# MUS-1099.net
KiCad netlist of a schematic drawn in EAGLE
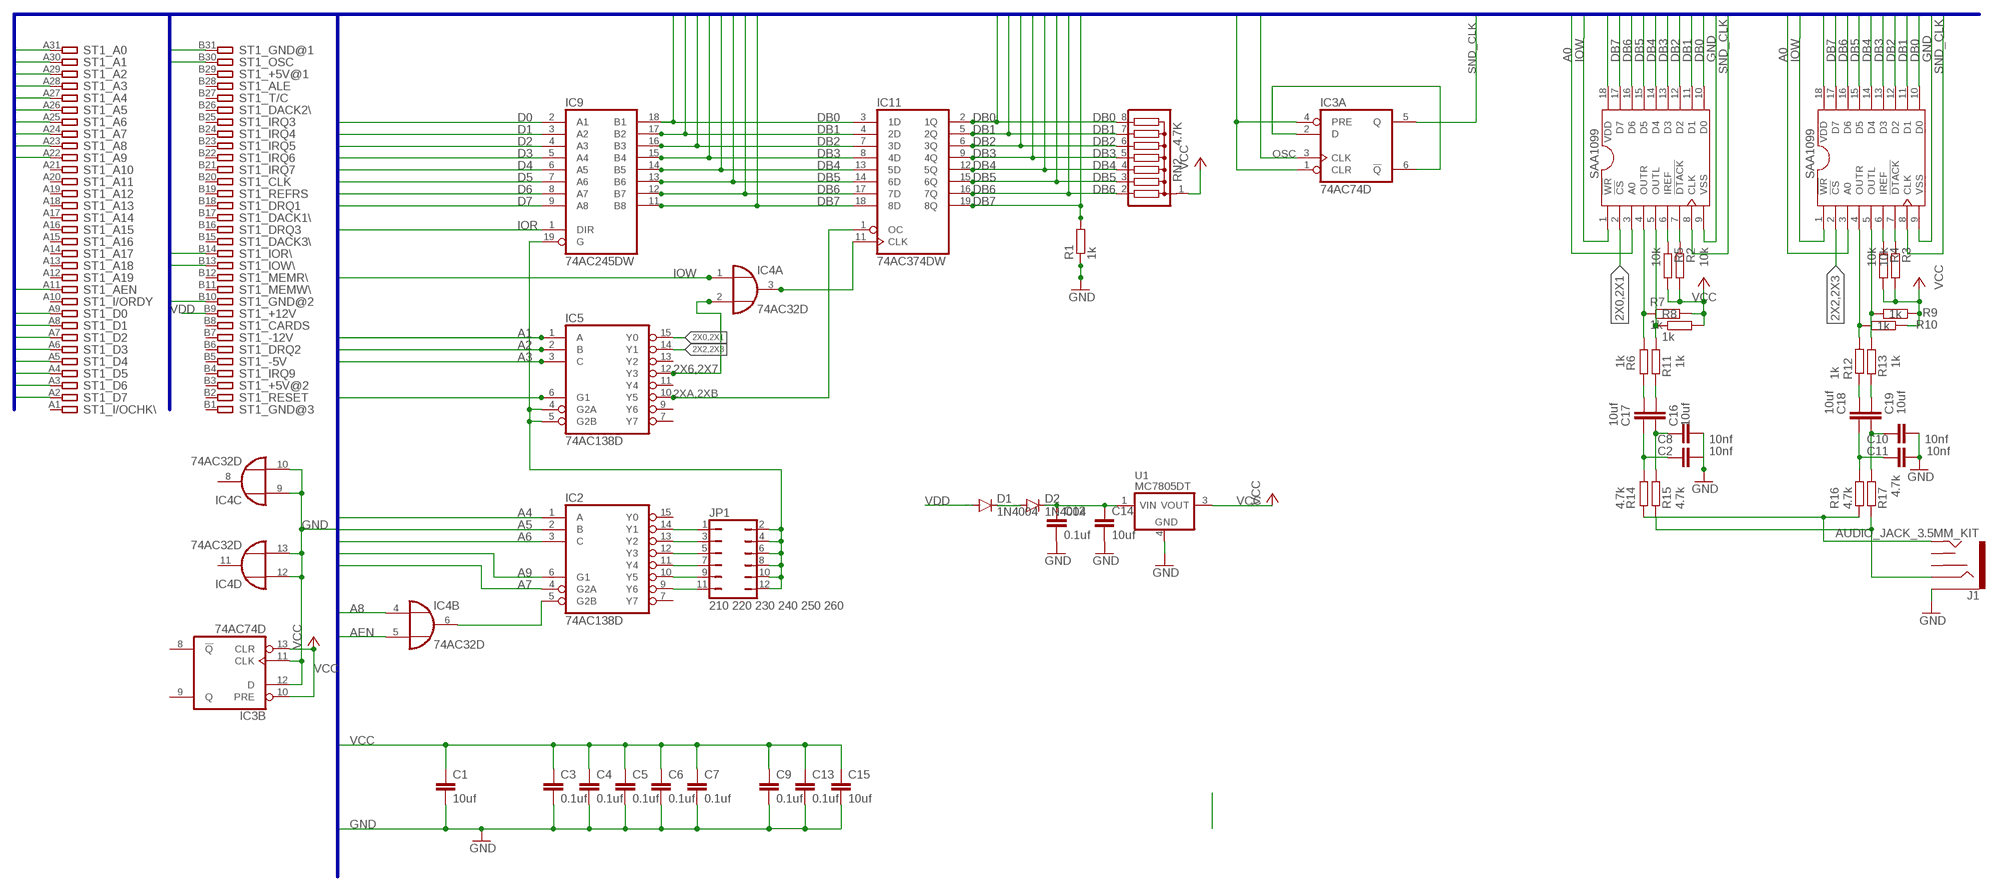
[diagram p0: schematic, sheet 1]

(export (version "E")
  (design (tool "Eeschema 10.0.6"))
  (components
    (comp (ref "C1")
      (value "10uf")
      (footprint "eagle-import:C0805")
      (libsource (lib "eagle-import") (part "C-EUC0805"))
    )
    (comp (ref "C2")
      (value "10nf")
      (footprint "eagle-import:C0805K")
      (libsource (lib "eagle-import") (part "C-EUC0805K"))
    )
    (comp (ref "C3")
      (value "0.1uf")
      (footprint "eagle-import:C0805")
      (libsource (lib "eagle-import") (part "C-EUC0805"))
    )
    (comp (ref "C4")
      (value "0.1uf")
      (footprint "eagle-import:C0805")
      (libsource (lib "eagle-import") (part "C-EUC0805"))
    )
    (comp (ref "C5")
      (value "0.1uf")
      (footprint "eagle-import:C0805")
      (libsource (lib "eagle-import") (part "C-EUC0805"))
    )
    (comp (ref "C6")
      (value "0.1uf")
      (footprint "eagle-import:C0805")
      (libsource (lib "eagle-import") (part "C-EUC0805"))
    )
    (comp (ref "C7")
      (value "0.1uf")
      (footprint "eagle-import:C0805")
      (libsource (lib "eagle-import") (part "C-EUC0805"))
    )
    (comp (ref "C8")
      (value "10nf")
      (footprint "eagle-import:C0805K")
      (libsource (lib "eagle-import") (part "C-EUC0805K"))
    )
    (comp (ref "C9")
      (value "0.1uf")
      (footprint "eagle-import:C0805")
      (libsource (lib "eagle-import") (part "C-EUC0805"))
    )
    (comp (ref "C10")
      (value "10nf")
      (footprint "eagle-import:C0805K")
      (libsource (lib "eagle-import") (part "C-EUC0805K"))
    )
    (comp (ref "C11")
      (value "10nf")
      (footprint "eagle-import:C0805K")
      (libsource (lib "eagle-import") (part "C-EUC0805K"))
    )
    (comp (ref "C12")
      (value "0.1uf")
      (footprint "eagle-import:C0805")
      (libsource (lib "eagle-import") (part "C-EUC0805"))
    )
    (comp (ref "C13")
      (value "0.1uf")
      (footprint "eagle-import:C0805")
      (libsource (lib "eagle-import") (part "C-EUC0805"))
    )
    (comp (ref "C14")
      (value "10uf")
      (footprint "eagle-import:C0805K")
      (libsource (lib "eagle-import") (part "C-EUC0805K"))
    )
    (comp (ref "C15")
      (value "10uf")
      (footprint "eagle-import:C0805K")
      (libsource (lib "eagle-import") (part "C-EUC0805K"))
    )
    (comp (ref "C16")
      (value "10uf")
      (footprint "eagle-import:C0805K")
      (libsource (lib "eagle-import") (part "C-EUC0805K"))
    )
    (comp (ref "C17")
      (value "10uf")
      (footprint "eagle-import:C0805K")
      (libsource (lib "eagle-import") (part "C-EUC0805K"))
    )
    (comp (ref "C18")
      (value "10uf")
      (footprint "eagle-import:C0805K")
      (libsource (lib "eagle-import") (part "C-EUC0805K"))
    )
    (comp (ref "C19")
      (value "10uf")
      (footprint "eagle-import:C0805K")
      (libsource (lib "eagle-import") (part "C-EUC0805K"))
    )
    (comp (ref "D1")
      (value "1N4004")
      (footprint "eagle-import:DO41-10")
      (libsource (lib "eagle-import") (part "1N4004"))
    )
    (comp (ref "D2")
      (value "1N4004")
      (footprint "eagle-import:DO41-10")
      (libsource (lib "eagle-import") (part "1N4004"))
    )
    (comp (ref "IC2")
      (value "74AC138D")
      (footprint "eagle-import:SO16")
      (libsource (lib "eagle-import") (part "74138DAC"))
    )
    (comp (ref "IC3")
      (value "74AC74D")
      (footprint "eagle-import:SO14")
      (libsource (lib "eagle-import") (part "7474DAC"))
    )
    (comp (ref "IC4")
      (value "74AC32D")
      (footprint "eagle-import:SO14")
      (libsource (lib "eagle-import") (part "7432DAC"))
    )
    (comp (ref "IC5")
      (value "74AC138D")
      (footprint "eagle-import:SO16")
      (libsource (lib "eagle-import") (part "74138DAC"))
    )
    (comp (ref "IC7")
      (value "SAA1099")
      (footprint "eagle-import:DIL18")
      (libsource (lib "eagle-import") (part "SAA1099"))
    )
    (comp (ref "IC8")
      (value "SAA1099")
      (footprint "eagle-import:DIL18")
      (libsource (lib "eagle-import") (part "SAA1099"))
    )
    (comp (ref "IC9")
      (value "74AC245DW")
      (footprint "eagle-import:SO20W")
      (libsource (lib "eagle-import") (part "74245DWAC"))
    )
    (comp (ref "IC11")
      (value "74AC374DW")
      (footprint "eagle-import:SO20W")
      (libsource (lib "eagle-import") (part "74374DWAC"))
    )
    (comp (ref "J1")
      (value "AUDIO_JACK_3.5MM_KIT")
      (footprint "eagle-import:AUDIO-JACK-KIT")
      (libsource (lib "eagle-import") (part "AUDIO_JACK_3.5MM_KIT"))
    )
    (comp (ref "JP1")
      (value "210 220 230 240 250 260")
      (footprint "eagle-import:JP6Q")
      (libsource (lib "eagle-import") (part "JP6Q"))
    )
    (comp (ref "R1")
      (value "1k")
      (footprint "eagle-import:R0805")
      (libsource (lib "eagle-import") (part "R-EU_R0805"))
    )
    (comp (ref "R2")
      (value "10k")
      (footprint "eagle-import:R0805")
      (libsource (lib "eagle-import") (part "R-EU_R0805"))
    )
    (comp (ref "R3")
      (value "10k")
      (footprint "eagle-import:R0805")
      (libsource (lib "eagle-import") (part "R-EU_R0805"))
    )
    (comp (ref "R4")
      (value "10k")
      (footprint "eagle-import:R0805")
      (libsource (lib "eagle-import") (part "R-EU_R0805"))
    )
    (comp (ref "R5")
      (value "10k")
      (footprint "eagle-import:R0805")
      (libsource (lib "eagle-import") (part "R-EU_R0805"))
    )
    (comp (ref "R6")
      (value "1k")
      (footprint "eagle-import:R0805")
      (libsource (lib "eagle-import") (part "R-EU_R0805"))
    )
    (comp (ref "R7")
      (value "1k")
      (footprint "eagle-import:R0805")
      (libsource (lib "eagle-import") (part "R-EU_R0805"))
    )
    (comp (ref "R8")
      (value "1k")
      (footprint "eagle-import:R0805")
      (libsource (lib "eagle-import") (part "R-EU_R0805"))
    )
    (comp (ref "R9")
      (value "1k")
      (footprint "eagle-import:R0805")
      (libsource (lib "eagle-import") (part "R-EU_R0805"))
    )
    (comp (ref "R10")
      (value "1k")
      (footprint "eagle-import:R0805")
      (libsource (lib "eagle-import") (part "R-EU_R0805"))
    )
    (comp (ref "R11")
      (value "1k")
      (footprint "eagle-import:R0805")
      (libsource (lib "eagle-import") (part "R-EU_R0805"))
    )
    (comp (ref "R12")
      (value "1k")
      (footprint "eagle-import:R0805")
      (libsource (lib "eagle-import") (part "R-EU_R0805"))
    )
    (comp (ref "R13")
      (value "1k")
      (footprint "eagle-import:R0805")
      (libsource (lib "eagle-import") (part "R-EU_R0805"))
    )
    (comp (ref "R14")
      (value "4.7k")
      (footprint "eagle-import:R0805")
      (libsource (lib "eagle-import") (part "R-EU_R0805"))
    )
    (comp (ref "R15")
      (value "4.7k")
      (footprint "eagle-import:R0805")
      (libsource (lib "eagle-import") (part "R-EU_R0805"))
    )
    (comp (ref "R16")
      (value "4.7k")
      (footprint "eagle-import:R0805")
      (libsource (lib "eagle-import") (part "R-EU_R0805"))
    )
    (comp (ref "R17")
      (value "4.7k")
      (footprint "eagle-import:R0805")
      (libsource (lib "eagle-import") (part "R-EU_R0805"))
    )
    (comp (ref "RN2")
      (value "4.7K")
      (footprint "eagle-import:SIL8")
      (libsource (lib "eagle-import") (part "G07R"))
    )
    (comp (ref "ST1")
      (value "8 bit ISA")
      (footprint "eagle-import:IBM8BIT")
      (libsource (lib "eagle-import") (part "IBM8BIT"))
    )
    (comp (ref "U1")
      (value "MC7805DT")
      (footprint "eagle-import:DPAK-3")
      (libsource (lib "eagle-import") (part "MC78DT05"))
    )
  )
  (nets
    (net (code "1") (name "/2X6,2X7") (class "Default")
      (node (ref "IC4") (pin "2") (pinfunction "I1_2") (pintype "input"))
      (node (ref "IC5") (pin "12") (pinfunction "Y3_12") (pintype "output"))
    )
    (net (code "2") (name "/2XA,2XB") (class "Default")
      (node (ref "IC11") (pin "1") (pinfunction "OC_1") (pintype "input"))
      (node (ref "IC5") (pin "10") (pinfunction "Y5_10") (pintype "output"))
    )
    (net (code "3") (name "/A0") (class "Default")
      (node (ref "IC7") (pin "3") (pinfunction "A0_3") (pintype "bidirectional"))
      (node (ref "IC8") (pin "3") (pinfunction "A0_3") (pintype "bidirectional"))
      (node (ref "ST1") (pin "A31") (pinfunction "P_A31") (pintype "bidirectional"))
    )
    (net (code "4") (name "/A1") (class "Default")
      (node (ref "IC5") (pin "1") (pinfunction "A_1") (pintype "input"))
      (node (ref "ST1") (pin "A30") (pinfunction "P_A30") (pintype "bidirectional"))
    )
    (net (code "5") (name "/A2") (class "Default")
      (node (ref "IC5") (pin "2") (pinfunction "B_2") (pintype "input"))
      (node (ref "ST1") (pin "A29") (pinfunction "P_A29") (pintype "bidirectional"))
    )
    (net (code "6") (name "/A3") (class "Default")
      (node (ref "IC5") (pin "3") (pinfunction "C_3") (pintype "input"))
      (node (ref "ST1") (pin "A28") (pinfunction "P_A28") (pintype "bidirectional"))
    )
    (net (code "7") (name "/A4") (class "Default")
      (node (ref "IC2") (pin "1") (pinfunction "A_1") (pintype "input"))
      (node (ref "ST1") (pin "A27") (pinfunction "P_A27") (pintype "bidirectional"))
    )
    (net (code "8") (name "/A5") (class "Default")
      (node (ref "IC2") (pin "2") (pinfunction "B_2") (pintype "input"))
      (node (ref "ST1") (pin "A26") (pinfunction "P_A26") (pintype "bidirectional"))
    )
    (net (code "9") (name "/A6") (class "Default")
      (node (ref "IC2") (pin "3") (pinfunction "C_3") (pintype "input"))
      (node (ref "ST1") (pin "A25") (pinfunction "P_A25") (pintype "bidirectional"))
    )
    (net (code "10") (name "/A7") (class "Default")
      (node (ref "IC2") (pin "4") (pinfunction "G2A_4") (pintype "input"))
      (node (ref "ST1") (pin "A24") (pinfunction "P_A24") (pintype "bidirectional"))
    )
    (net (code "11") (name "/A8") (class "Default")
      (node (ref "IC4") (pin "4") (pinfunction "I0_4") (pintype "input"))
      (node (ref "ST1") (pin "A23") (pinfunction "P_A23") (pintype "bidirectional"))
    )
    (net (code "12") (name "/A9") (class "Default")
      (node (ref "IC2") (pin "6") (pinfunction "G1_6") (pintype "input"))
      (node (ref "ST1") (pin "A22") (pinfunction "P_A22") (pintype "bidirectional"))
    )
    (net (code "13") (name "/AEN") (class "Default")
      (node (ref "IC4") (pin "5") (pinfunction "I1_5") (pintype "input"))
      (node (ref "ST1") (pin "A11") (pinfunction "P_A11") (pintype "bidirectional"))
    )
    (net (code "14") (name "/D0") (class "Default")
      (node (ref "IC9") (pin "2") (pinfunction "A1_2") (pintype "bidirectional"))
      (node (ref "ST1") (pin "A9") (pinfunction "P_A9") (pintype "bidirectional"))
    )
    (net (code "15") (name "/D1") (class "Default")
      (node (ref "IC9") (pin "3") (pinfunction "A2_3") (pintype "bidirectional"))
      (node (ref "ST1") (pin "A8") (pinfunction "P_A8") (pintype "bidirectional"))
    )
    (net (code "16") (name "/D2") (class "Default")
      (node (ref "IC9") (pin "4") (pinfunction "A3_4") (pintype "bidirectional"))
      (node (ref "ST1") (pin "A7") (pinfunction "P_A7") (pintype "bidirectional"))
    )
    (net (code "17") (name "/D3") (class "Default")
      (node (ref "IC9") (pin "5") (pinfunction "A4_5") (pintype "bidirectional"))
      (node (ref "ST1") (pin "A6") (pinfunction "P_A6") (pintype "bidirectional"))
    )
    (net (code "18") (name "/D4") (class "Default")
      (node (ref "IC9") (pin "6") (pinfunction "A5_6") (pintype "bidirectional"))
      (node (ref "ST1") (pin "A5") (pinfunction "P_A5") (pintype "bidirectional"))
    )
    (net (code "19") (name "/D5") (class "Default")
      (node (ref "IC9") (pin "7") (pinfunction "A6_7") (pintype "bidirectional"))
      (node (ref "ST1") (pin "A4") (pinfunction "P_A4") (pintype "bidirectional"))
    )
    (net (code "20") (name "/D6") (class "Default")
      (node (ref "IC9") (pin "8") (pinfunction "A7_8") (pintype "bidirectional"))
      (node (ref "ST1") (pin "A3") (pinfunction "P_A3") (pintype "bidirectional"))
    )
    (net (code "21") (name "/D7") (class "Default")
      (node (ref "IC9") (pin "9") (pinfunction "A8_9") (pintype "bidirectional"))
      (node (ref "ST1") (pin "A2") (pinfunction "P_A2") (pintype "bidirectional"))
    )
    (net (code "22") (name "/DB0") (class "Default")
      (node (ref "IC11") (pin "2") (pinfunction "1Q_2") (pintype "tri_state"))
      (node (ref "IC11") (pin "3") (pinfunction "1D_3") (pintype "input"))
      (node (ref "IC7") (pin "10") (pinfunction "D0_10") (pintype "bidirectional"))
      (node (ref "IC8") (pin "10") (pinfunction "D0_10") (pintype "bidirectional"))
      (node (ref "IC9") (pin "18") (pinfunction "B1_18") (pintype "bidirectional"))
      (node (ref "RN2") (pin "8") (pinfunction "8_8") (pintype "passive"))
    )
    (net (code "23") (name "/DB1") (class "Default")
      (node (ref "IC11") (pin "4") (pinfunction "2D_4") (pintype "input"))
      (node (ref "IC11") (pin "5") (pinfunction "2Q_5") (pintype "tri_state"))
      (node (ref "IC7") (pin "11") (pinfunction "D1_11") (pintype "bidirectional"))
      (node (ref "IC8") (pin "11") (pinfunction "D1_11") (pintype "bidirectional"))
      (node (ref "IC9") (pin "17") (pinfunction "B2_17") (pintype "bidirectional"))
      (node (ref "RN2") (pin "7") (pinfunction "7_7") (pintype "passive"))
    )
    (net (code "24") (name "/DB2") (class "Default")
      (node (ref "IC11") (pin "6") (pinfunction "3Q_6") (pintype "tri_state"))
      (node (ref "IC11") (pin "7") (pinfunction "3D_7") (pintype "input"))
      (node (ref "IC7") (pin "12") (pinfunction "D2_12") (pintype "bidirectional"))
      (node (ref "IC8") (pin "12") (pinfunction "D2_12") (pintype "bidirectional"))
      (node (ref "IC9") (pin "16") (pinfunction "B3_16") (pintype "bidirectional"))
      (node (ref "RN2") (pin "6") (pinfunction "6_6") (pintype "passive"))
    )
    (net (code "25") (name "/DB3") (class "Default")
      (node (ref "IC11") (pin "8") (pinfunction "4D_8") (pintype "input"))
      (node (ref "IC11") (pin "9") (pinfunction "4Q_9") (pintype "tri_state"))
      (node (ref "IC7") (pin "13") (pinfunction "D3_13") (pintype "bidirectional"))
      (node (ref "IC8") (pin "13") (pinfunction "D3_13") (pintype "bidirectional"))
      (node (ref "IC9") (pin "15") (pinfunction "B4_15") (pintype "bidirectional"))
      (node (ref "RN2") (pin "5") (pinfunction "5_5") (pintype "passive"))
    )
    (net (code "26") (name "/DB4") (class "Default")
      (node (ref "IC11") (pin "12") (pinfunction "5Q_12") (pintype "tri_state"))
      (node (ref "IC11") (pin "13") (pinfunction "5D_13") (pintype "input"))
      (node (ref "IC7") (pin "14") (pinfunction "D4_14") (pintype "bidirectional"))
      (node (ref "IC8") (pin "14") (pinfunction "D4_14") (pintype "bidirectional"))
      (node (ref "IC9") (pin "14") (pinfunction "B5_14") (pintype "bidirectional"))
      (node (ref "RN2") (pin "4") (pinfunction "4_4") (pintype "passive"))
    )
    (net (code "27") (name "/DB5") (class "Default")
      (node (ref "IC11") (pin "14") (pinfunction "6D_14") (pintype "input"))
      (node (ref "IC11") (pin "15") (pinfunction "6Q_15") (pintype "tri_state"))
      (node (ref "IC7") (pin "15") (pinfunction "D5_15") (pintype "bidirectional"))
      (node (ref "IC8") (pin "15") (pinfunction "D5_15") (pintype "bidirectional"))
      (node (ref "IC9") (pin "13") (pinfunction "B6_13") (pintype "bidirectional"))
      (node (ref "RN2") (pin "3") (pinfunction "3_3") (pintype "passive"))
    )
    (net (code "28") (name "/DB6") (class "Default")
      (node (ref "IC11") (pin "16") (pinfunction "7Q_16") (pintype "tri_state"))
      (node (ref "IC11") (pin "17") (pinfunction "7D_17") (pintype "input"))
      (node (ref "IC7") (pin "16") (pinfunction "D6_16") (pintype "bidirectional"))
      (node (ref "IC8") (pin "16") (pinfunction "D6_16") (pintype "bidirectional"))
      (node (ref "IC9") (pin "12") (pinfunction "B7_12") (pintype "bidirectional"))
      (node (ref "RN2") (pin "2") (pinfunction "2_2") (pintype "passive"))
    )
    (net (code "29") (name "/DB7") (class "Default")
      (node (ref "IC11") (pin "18") (pinfunction "8D_18") (pintype "input"))
      (node (ref "IC11") (pin "19") (pinfunction "8Q_19") (pintype "tri_state"))
      (node (ref "IC7") (pin "17") (pinfunction "D7_17") (pintype "bidirectional"))
      (node (ref "IC8") (pin "17") (pinfunction "D7_17") (pintype "bidirectional"))
      (node (ref "IC9") (pin "11") (pinfunction "B8_11") (pintype "bidirectional"))
      (node (ref "R1") (pin "2") (pinfunction "2_2") (pintype "passive"))
    )
    (net (code "30") (name "/IOR") (class "Default")
      (node (ref "IC9") (pin "1") (pinfunction "DIR_1") (pintype "input"))
      (node (ref "ST1") (pin "B14") (pinfunction "P_B14") (pintype "bidirectional"))
    )
    (net (code "31") (name "/IOW") (class "Default")
      (node (ref "IC4") (pin "1") (pinfunction "I0_1") (pintype "input"))
      (node (ref "IC7") (pin "1") (pinfunction "~{WR}_1") (pintype "bidirectional"))
      (node (ref "IC8") (pin "1") (pinfunction "~{WR}_1") (pintype "bidirectional"))
      (node (ref "ST1") (pin "B13") (pinfunction "P_B13") (pintype "bidirectional"))
    )
    (net (code "32") (name "/OSC") (class "Default")
      (node (ref "IC3") (pin "3") (pinfunction "CLK_3") (pintype "input"))
      (node (ref "ST1") (pin "B30") (pinfunction "P_B30") (pintype "bidirectional"))
    )
    (net (code "33") (name "/SND_CLK") (class "Default")
      (node (ref "IC3") (pin "5") (pinfunction "Q_5") (pintype "output"))
      (node (ref "IC7") (pin "8") (pinfunction "CLK_8") (pintype "bidirectional"))
      (node (ref "IC8") (pin "8") (pinfunction "CLK_8") (pintype "bidirectional"))
    )
    (net (code "34") (name "/VDD") (class "Default")
      (node (ref "D1") (pin "A") (pinfunction "A_A") (pintype "passive"))
      (node (ref "ST1") (pin "B9") (pinfunction "P_B9") (pintype "bidirectional"))
    )
    (net (code "35") (name "2X0,2X1") (class "Default")
      (node (ref "IC5") (pin "15") (pinfunction "Y0_15") (pintype "output"))
      (node (ref "IC7") (pin "2") (pinfunction "~{CS}_2") (pintype "bidirectional"))
    )
    (net (code "36") (name "2X2,2X3") (class "Default")
      (node (ref "IC5") (pin "14") (pinfunction "Y1_14") (pintype "output"))
      (node (ref "IC8") (pin "2") (pinfunction "~{CS}_2") (pintype "bidirectional"))
    )
    (net (code "37") (name "GND") (class "Default")
      (node (ref "C1") (pin "2") (pinfunction "2_2") (pintype "passive"))
      (node (ref "C10") (pin "2") (pinfunction "2_2") (pintype "passive"))
      (node (ref "C11") (pin "2") (pinfunction "2_2") (pintype "passive"))
      (node (ref "C12") (pin "2") (pinfunction "2_2") (pintype "passive"))
      (node (ref "C13") (pin "2") (pinfunction "2_2") (pintype "passive"))
      (node (ref "C14") (pin "2") (pinfunction "2_2") (pintype "passive"))
      (node (ref "C15") (pin "2") (pinfunction "2_2") (pintype "passive"))
      (node (ref "C2") (pin "2") (pinfunction "2_2") (pintype "passive"))
      (node (ref "C3") (pin "2") (pinfunction "2_2") (pintype "passive"))
      (node (ref "C4") (pin "2") (pinfunction "2_2") (pintype "passive"))
      (node (ref "C5") (pin "2") (pinfunction "2_2") (pintype "passive"))
      (node (ref "C6") (pin "2") (pinfunction "2_2") (pintype "passive"))
      (node (ref "C7") (pin "2") (pinfunction "2_2") (pintype "passive"))
      (node (ref "C8") (pin "2") (pinfunction "2_2") (pintype "passive"))
      (node (ref "C9") (pin "2") (pinfunction "2_2") (pintype "passive"))
      (node (ref "IC3") (pin "11") (pinfunction "CLK_11") (pintype "input"))
      (node (ref "IC3") (pin "12") (pinfunction "D_12") (pintype "input"))
      (node (ref "IC4") (pin "10") (pinfunction "I1_10") (pintype "input"))
      (node (ref "IC4") (pin "12") (pinfunction "I0_12") (pintype "input"))
      (node (ref "IC4") (pin "13") (pinfunction "I1_13") (pintype "input"))
      (node (ref "IC4") (pin "9") (pinfunction "I0_9") (pintype "input"))
      (node (ref "IC7") (pin "9") (pinfunction "VSS_9") (pintype "bidirectional"))
      (node (ref "IC8") (pin "9") (pinfunction "VSS_9") (pintype "bidirectional"))
      (node (ref "J1") (pin "SLEEVE") (pinfunction "SLEEVE_SLEEVE") (pintype "bidirectional"))
      (node (ref "R1") (pin "1") (pinfunction "1_1") (pintype "passive"))
      (node (ref "ST1") (pin "B10") (pinfunction "P_B10") (pintype "bidirectional"))
      (node (ref "ST1") (pin "B31") (pinfunction "P_B31") (pintype "bidirectional"))
      (node (ref "U1") (pin "4") (pinfunction "GND_4") (pintype "power_in"))
    )
    (net (code "38") (name "Net-(C10-Pad1)") (class "Default")
      (node (ref "C10") (pin "1") (pinfunction "1_1") (pintype "passive"))
      (node (ref "C19") (pin "2") (pinfunction "2_2") (pintype "passive"))
      (node (ref "R17") (pin "1") (pinfunction "1_1") (pintype "passive"))
    )
    (net (code "39") (name "Net-(C11-Pad1)") (class "Default")
      (node (ref "C11") (pin "1") (pinfunction "1_1") (pintype "passive"))
      (node (ref "C18") (pin "2") (pinfunction "2_2") (pintype "passive"))
      (node (ref "R16") (pin "1") (pinfunction "1_1") (pintype "passive"))
    )
    (net (code "40") (name "Net-(C16-Pad1)") (class "Default")
      (node (ref "C16") (pin "1") (pinfunction "1_1") (pintype "passive"))
      (node (ref "R11") (pin "2") (pinfunction "2_2") (pintype "passive"))
    )
    (net (code "41") (name "Net-(C16-Pad2)") (class "Default")
      (node (ref "C16") (pin "2") (pinfunction "2_2") (pintype "passive"))
      (node (ref "C8") (pin "1") (pinfunction "1_1") (pintype "passive"))
      (node (ref "R15") (pin "1") (pinfunction "1_1") (pintype "passive"))
    )
    (net (code "42") (name "Net-(C17-Pad1)") (class "Default")
      (node (ref "C17") (pin "1") (pinfunction "1_1") (pintype "passive"))
      (node (ref "R6") (pin "2") (pinfunction "2_2") (pintype "passive"))
    )
    (net (code "43") (name "Net-(C17-Pad2)") (class "Default")
      (node (ref "C17") (pin "2") (pinfunction "2_2") (pintype "passive"))
      (node (ref "C2") (pin "1") (pinfunction "1_1") (pintype "passive"))
      (node (ref "R14") (pin "1") (pinfunction "1_1") (pintype "passive"))
    )
    (net (code "44") (name "Net-(C18-Pad1)") (class "Default")
      (node (ref "C18") (pin "1") (pinfunction "1_1") (pintype "passive"))
      (node (ref "R12") (pin "1") (pinfunction "1_1") (pintype "passive"))
    )
    (net (code "45") (name "Net-(C19-Pad1)") (class "Default")
      (node (ref "C19") (pin "1") (pinfunction "1_1") (pintype "passive"))
      (node (ref "R13") (pin "2") (pinfunction "2_2") (pintype "passive"))
    )
    (net (code "46") (name "Net-(D1-PadC)") (class "Default")
      (node (ref "D1") (pin "C") (pinfunction "C_C") (pintype "passive"))
      (node (ref "D2") (pin "A") (pinfunction "A_A") (pintype "passive"))
    )
    (net (code "47") (name "Net-(IC2A-G2B)") (class "Default")
      (node (ref "IC2") (pin "5") (pinfunction "G2B_5") (pintype "input"))
      (node (ref "IC4") (pin "6") (pinfunction "O_6") (pintype "output"))
    )
    (net (code "48") (name "Net-(IC2A-Y1)") (class "Default")
      (node (ref "IC2") (pin "14") (pinfunction "Y1_14") (pintype "output"))
      (node (ref "JP1") (pin "1") (pinfunction "1_1") (pintype "passive"))
    )
    (net (code "49") (name "Net-(IC2A-Y2)") (class "Default")
      (node (ref "IC2") (pin "13") (pinfunction "Y2_13") (pintype "output"))
      (node (ref "JP1") (pin "3") (pinfunction "3_3") (pintype "passive"))
    )
    (net (code "50") (name "Net-(IC2A-Y3)") (class "Default")
      (node (ref "IC2") (pin "12") (pinfunction "Y3_12") (pintype "output"))
      (node (ref "JP1") (pin "5") (pinfunction "5_5") (pintype "passive"))
    )
    (net (code "51") (name "Net-(IC2A-Y4)") (class "Default")
      (node (ref "IC2") (pin "11") (pinfunction "Y4_11") (pintype "output"))
      (node (ref "JP1") (pin "7") (pinfunction "7_7") (pintype "passive"))
    )
    (net (code "52") (name "Net-(IC2A-Y5)") (class "Default")
      (node (ref "IC2") (pin "10") (pinfunction "Y5_10") (pintype "output"))
      (node (ref "JP1") (pin "9") (pinfunction "9_9") (pintype "passive"))
    )
    (net (code "53") (name "Net-(IC2A-Y6)") (class "Default")
      (node (ref "IC2") (pin "9") (pinfunction "Y6_9") (pintype "output"))
      (node (ref "JP1") (pin "11") (pinfunction "11_11") (pintype "passive"))
    )
    (net (code "54") (name "Net-(IC3A-D)") (class "Default")
      (node (ref "IC3") (pin "2") (pinfunction "D_2") (pintype "input"))
      (node (ref "IC3") (pin "6") (pinfunction "~{Q}_6") (pintype "output"))
    )
    (net (code "55") (name "Net-(IC5A-G2A)") (class "Default")
      (node (ref "IC5") (pin "4") (pinfunction "G2A_4") (pintype "input"))
      (node (ref "IC5") (pin "5") (pinfunction "G2B_5") (pintype "input"))
      (node (ref "IC9") (pin "19") (pinfunction "G_19") (pintype "input"))
      (node (ref "JP1") (pin "10") (pinfunction "10_10") (pintype "passive"))
      (node (ref "JP1") (pin "12") (pinfunction "12_12") (pintype "passive"))
      (node (ref "JP1") (pin "2") (pinfunction "2_2") (pintype "passive"))
      (node (ref "JP1") (pin "4") (pinfunction "4_4") (pintype "passive"))
      (node (ref "JP1") (pin "6") (pinfunction "6_6") (pintype "passive"))
      (node (ref "JP1") (pin "8") (pinfunction "8_8") (pintype "passive"))
    )
    (net (code "56") (name "Net-(IC7-IREF)") (class "Default")
      (node (ref "IC7") (pin "6") (pinfunction "IREF_6") (pintype "bidirectional"))
      (node (ref "R5") (pin "1") (pinfunction "1_1") (pintype "passive"))
    )
    (net (code "57") (name "Net-(IC7-OUTL)") (class "Default")
      (node (ref "IC7") (pin "5") (pinfunction "OUTL_5") (pintype "passive"))
      (node (ref "R11") (pin "1") (pinfunction "1_1") (pintype "passive"))
      (node (ref "R8") (pin "1") (pinfunction "1_1") (pintype "passive"))
    )
    (net (code "58") (name "Net-(IC7-OUTR)") (class "Default")
      (node (ref "IC7") (pin "4") (pinfunction "OUTR_4") (pintype "passive"))
      (node (ref "R6") (pin "1") (pinfunction "1_1") (pintype "passive"))
      (node (ref "R7") (pin "1") (pinfunction "1_1") (pintype "passive"))
    )
    (net (code "59") (name "Net-(IC7-~{DTACK})") (class "Default")
      (node (ref "IC7") (pin "7") (pinfunction "~{DTACK}_7") (pintype "bidirectional"))
      (node (ref "R2") (pin "1") (pinfunction "1_1") (pintype "passive"))
    )
    (net (code "60") (name "Net-(IC8-IREF)") (class "Default")
      (node (ref "IC8") (pin "6") (pinfunction "IREF_6") (pintype "bidirectional"))
      (node (ref "R4") (pin "1") (pinfunction "1_1") (pintype "passive"))
    )
    (net (code "61") (name "Net-(IC8-OUTL)") (class "Default")
      (node (ref "IC8") (pin "5") (pinfunction "OUTL_5") (pintype "passive"))
      (node (ref "R13") (pin "1") (pinfunction "1_1") (pintype "passive"))
      (node (ref "R9") (pin "2") (pinfunction "2_2") (pintype "passive"))
    )
    (net (code "62") (name "Net-(IC8-OUTR)") (class "Default")
      (node (ref "IC8") (pin "4") (pinfunction "OUTR_4") (pintype "passive"))
      (node (ref "R10") (pin "2") (pinfunction "2_2") (pintype "passive"))
      (node (ref "R12") (pin "2") (pinfunction "2_2") (pintype "passive"))
    )
    (net (code "63") (name "Net-(IC8-~{DTACK})") (class "Default")
      (node (ref "IC8") (pin "7") (pinfunction "~{DTACK}_7") (pintype "bidirectional"))
      (node (ref "R3") (pin "1") (pinfunction "1_1") (pintype "passive"))
    )
    (net (code "64") (name "Net-(IC11A-CLK)") (class "Default")
      (node (ref "IC11") (pin "11") (pinfunction "CLK_11") (pintype "input"))
      (node (ref "IC4") (pin "3") (pinfunction "O_3") (pintype "output"))
    )
    (net (code "65") (name "Net-(J1-PadRING)") (class "Default")
      (node (ref "J1") (pin "RING") (pinfunction "RING_RING") (pintype "bidirectional"))
      (node (ref "R15") (pin "2") (pinfunction "2_2") (pintype "passive"))
      (node (ref "R17") (pin "2") (pinfunction "2_2") (pintype "passive"))
    )
    (net (code "66") (name "Net-(J1-PadTIP)") (class "Default")
      (node (ref "J1") (pin "TIP") (pinfunction "TIP_TIP") (pintype "bidirectional"))
      (node (ref "R14") (pin "2") (pinfunction "2_2") (pintype "passive"))
      (node (ref "R16") (pin "2") (pinfunction "2_2") (pintype "passive"))
    )
    (net (code "67") (name "Net-(U1-VIN)") (class "Default")
      (node (ref "C12") (pin "1") (pinfunction "1_1") (pintype "passive"))
      (node (ref "C14") (pin "1") (pinfunction "1_1") (pintype "passive"))
      (node (ref "D2") (pin "C") (pinfunction "C_C") (pintype "passive"))
      (node (ref "U1") (pin "1") (pinfunction "VIN_1") (pintype "power_in"))
    )
    (net (code "68") (name "VCC") (class "Default")
      (node (ref "C1") (pin "1") (pinfunction "1_1") (pintype "passive"))
      (node (ref "C13") (pin "1") (pinfunction "1_1") (pintype "passive"))
      (node (ref "C15") (pin "1") (pinfunction "1_1") (pintype "passive"))
      (node (ref "C3") (pin "1") (pinfunction "1_1") (pintype "passive"))
      (node (ref "C4") (pin "1") (pinfunction "1_1") (pintype "passive"))
      (node (ref "C5") (pin "1") (pinfunction "1_1") (pintype "passive"))
      (node (ref "C6") (pin "1") (pinfunction "1_1") (pintype "passive"))
      (node (ref "C7") (pin "1") (pinfunction "1_1") (pintype "passive"))
      (node (ref "C9") (pin "1") (pinfunction "1_1") (pintype "passive"))
      (node (ref "IC3") (pin "1") (pinfunction "CLR_1") (pintype "input"))
      (node (ref "IC3") (pin "10") (pinfunction "PRE_10") (pintype "input"))
      (node (ref "IC3") (pin "13") (pinfunction "CLR_13") (pintype "input"))
      (node (ref "IC3") (pin "4") (pinfunction "PRE_4") (pintype "input"))
      (node (ref "IC5") (pin "6") (pinfunction "G1_6") (pintype "input"))
      (node (ref "IC7") (pin "18") (pinfunction "VDD_18") (pintype "bidirectional"))
      (node (ref "IC8") (pin "18") (pinfunction "VDD_18") (pintype "bidirectional"))
      (node (ref "R10") (pin "1") (pinfunction "1_1") (pintype "passive"))
      (node (ref "R2") (pin "2") (pinfunction "2_2") (pintype "passive"))
      (node (ref "R3") (pin "2") (pinfunction "2_2") (pintype "passive"))
      (node (ref "R4") (pin "2") (pinfunction "2_2") (pintype "passive"))
      (node (ref "R5") (pin "2") (pinfunction "2_2") (pintype "passive"))
      (node (ref "R7") (pin "2") (pinfunction "2_2") (pintype "passive"))
      (node (ref "R8") (pin "2") (pinfunction "2_2") (pintype "passive"))
      (node (ref "R9") (pin "1") (pinfunction "1_1") (pintype "passive"))
      (node (ref "RN2") (pin "1") (pinfunction "1_1") (pintype "passive"))
      (node (ref "U1") (pin "3") (pinfunction "VOUT_3") (pintype "power_in"))
    )
    (net (code "69") (name "unconnected-(IC2A-Y0-Pad15)") (class "Default")
      (node (ref "IC2") (pin "15") (pinfunction "Y0_15") (pintype "output"))
    )
    (net (code "70") (name "unconnected-(IC2A-Y7-Pad7)") (class "Default")
      (node (ref "IC2") (pin "7") (pinfunction "Y7_7") (pintype "output"))
    )
    (net (code "71") (name "unconnected-(IC3B-Q-Pad9)") (class "Default")
      (node (ref "IC3") (pin "9") (pinfunction "Q_9") (pintype "output"))
    )
    (net (code "72") (name "unconnected-(IC3B-~{Q}-Pad8)") (class "Default")
      (node (ref "IC3") (pin "8") (pinfunction "~{Q}_8") (pintype "output"))
    )
    (net (code "73") (name "unconnected-(IC4C-O-Pad8)") (class "Default")
      (node (ref "IC4") (pin "8") (pinfunction "O_8") (pintype "output"))
    )
    (net (code "74") (name "unconnected-(IC4D-O-Pad11)") (class "Default")
      (node (ref "IC4") (pin "11") (pinfunction "O_11") (pintype "output"))
    )
    (net (code "75") (name "unconnected-(IC5A-Y2-Pad13)") (class "Default")
      (node (ref "IC5") (pin "13") (pinfunction "Y2_13") (pintype "output"))
    )
    (net (code "76") (name "unconnected-(IC5A-Y4-Pad11)") (class "Default")
      (node (ref "IC5") (pin "11") (pinfunction "Y4_11") (pintype "output"))
    )
    (net (code "77") (name "unconnected-(IC5A-Y6-Pad9)") (class "Default")
      (node (ref "IC5") (pin "9") (pinfunction "Y6_9") (pintype "output"))
    )
    (net (code "78") (name "unconnected-(IC5A-Y7-Pad7)") (class "Default")
      (node (ref "IC5") (pin "7") (pinfunction "Y7_7") (pintype "output"))
    )
    (net (code "79") (name "unconnected-(J1-PadRSH)") (class "Default")
      (node (ref "J1") (pin "RSH") (pinfunction "RSH_RSH") (pintype "bidirectional"))
    )
    (net (code "80") (name "unconnected-(J1-PadTSH)") (class "Default")
      (node (ref "J1") (pin "TSH") (pinfunction "TSH_TSH") (pintype "bidirectional"))
    )
    (net (code "81") (name "unconnected-(ST1AA-P-PadB28)") (class "Default")
      (node (ref "ST1") (pin "B28") (pinfunction "P_B28") (pintype "bidirectional"))
    )
    (net (code "82") (name "unconnected-(ST1AB-P-PadB8)") (class "Default")
      (node (ref "ST1") (pin "B8") (pinfunction "P_B8") (pintype "bidirectional"))
    )
    (net (code "83") (name "unconnected-(ST1AC-P-PadB20)") (class "Default")
      (node (ref "ST1") (pin "B20") (pinfunction "P_B20") (pintype "bidirectional"))
    )
    (net (code "84") (name "unconnected-(ST1AL-P-PadB17)") (class "Default")
      (node (ref "ST1") (pin "B17") (pinfunction "P_B17") (pintype "bidirectional"))
    )
    (net (code "85") (name "unconnected-(ST1AM-P-PadB26)") (class "Default")
      (node (ref "ST1") (pin "B26") (pinfunction "P_B26") (pintype "bidirectional"))
    )
    (net (code "86") (name "unconnected-(ST1AN-P-PadB15)") (class "Default")
      (node (ref "ST1") (pin "B15") (pinfunction "P_B15") (pintype "bidirectional"))
    )
    (net (code "87") (name "unconnected-(ST1AO-P-PadB18)") (class "Default")
      (node (ref "ST1") (pin "B18") (pinfunction "P_B18") (pintype "bidirectional"))
    )
    (net (code "88") (name "unconnected-(ST1AP-P-PadB6)") (class "Default")
      (node (ref "ST1") (pin "B6") (pinfunction "P_B6") (pintype "bidirectional"))
    )
    (net (code "89") (name "unconnected-(ST1AQ-P-PadB16)") (class "Default")
      (node (ref "ST1") (pin "B16") (pinfunction "P_B16") (pintype "bidirectional"))
    )
    (net (code "90") (name "unconnected-(ST1AT-P-PadB1)") (class "Default")
      (node (ref "ST1") (pin "B1") (pinfunction "P_B1") (pintype "bidirectional"))
    )
    (net (code "91") (name "unconnected-(ST1AU-P-PadA1)") (class "Default")
      (node (ref "ST1") (pin "A1") (pinfunction "P_A1") (pintype "bidirectional"))
    )
    (net (code "92") (name "unconnected-(ST1AV-P-PadA10)") (class "Default")
      (node (ref "ST1") (pin "A10") (pinfunction "P_A10") (pintype "bidirectional"))
    )
    (net (code "93") (name "unconnected-(ST1AY-P-PadB25)") (class "Default")
      (node (ref "ST1") (pin "B25") (pinfunction "P_B25") (pintype "bidirectional"))
    )
    (net (code "94") (name "unconnected-(ST1AZ-P-PadB24)") (class "Default")
      (node (ref "ST1") (pin "B24") (pinfunction "P_B24") (pintype "bidirectional"))
    )
    (net (code "95") (name "unconnected-(ST1B-P-PadB29)") (class "Default")
      (node (ref "ST1") (pin "B29") (pinfunction "P_B29") (pintype "bidirectional"))
    )
    (net (code "96") (name "unconnected-(ST1BA-P-PadB23)") (class "Default")
      (node (ref "ST1") (pin "B23") (pinfunction "P_B23") (pintype "bidirectional"))
    )
    (net (code "97") (name "unconnected-(ST1BB-P-PadB22)") (class "Default")
      (node (ref "ST1") (pin "B22") (pinfunction "P_B22") (pintype "bidirectional"))
    )
    (net (code "98") (name "unconnected-(ST1BC-P-PadB21)") (class "Default")
      (node (ref "ST1") (pin "B21") (pinfunction "P_B21") (pintype "bidirectional"))
    )
    (net (code "99") (name "unconnected-(ST1BD-P-PadB4)") (class "Default")
      (node (ref "ST1") (pin "B4") (pinfunction "P_B4") (pintype "bidirectional"))
    )
    (net (code "100") (name "unconnected-(ST1BE-P-PadB12)") (class "Default")
      (node (ref "ST1") (pin "B12") (pinfunction "P_B12") (pintype "bidirectional"))
    )
    (net (code "101") (name "unconnected-(ST1BF-P-PadB11)") (class "Default")
      (node (ref "ST1") (pin "B11") (pinfunction "P_B11") (pintype "bidirectional"))
    )
    (net (code "102") (name "unconnected-(ST1BH-P-PadB19)") (class "Default")
      (node (ref "ST1") (pin "B19") (pinfunction "P_B19") (pintype "bidirectional"))
    )
    (net (code "103") (name "unconnected-(ST1BI-P-PadB2)") (class "Default")
      (node (ref "ST1") (pin "B2") (pinfunction "P_B2") (pintype "bidirectional"))
    )
    (net (code "104") (name "unconnected-(ST1BJ-P-PadB27)") (class "Default")
      (node (ref "ST1") (pin "B27") (pinfunction "P_B27") (pintype "bidirectional"))
    )
    (net (code "105") (name "unconnected-(ST1C-P-PadB3)") (class "Default")
      (node (ref "ST1") (pin "B3") (pinfunction "P_B3") (pintype "bidirectional"))
    )
    (net (code "106") (name "unconnected-(ST1D-P-PadB7)") (class "Default")
      (node (ref "ST1") (pin "B7") (pinfunction "P_B7") (pintype "bidirectional"))
    )
    (net (code "107") (name "unconnected-(ST1E-P-PadB5)") (class "Default")
      (node (ref "ST1") (pin "B5") (pinfunction "P_B5") (pintype "bidirectional"))
    )
    (net (code "108") (name "unconnected-(ST1H-P-PadA21)") (class "Default")
      (node (ref "ST1") (pin "A21") (pinfunction "P_A21") (pintype "bidirectional"))
    )
    (net (code "109") (name "unconnected-(ST1I-P-PadA20)") (class "Default")
      (node (ref "ST1") (pin "A20") (pinfunction "P_A20") (pintype "bidirectional"))
    )
    (net (code "110") (name "unconnected-(ST1J-P-PadA19)") (class "Default")
      (node (ref "ST1") (pin "A19") (pinfunction "P_A19") (pintype "bidirectional"))
    )
    (net (code "111") (name "unconnected-(ST1K-P-PadA18)") (class "Default")
      (node (ref "ST1") (pin "A18") (pinfunction "P_A18") (pintype "bidirectional"))
    )
    (net (code "112") (name "unconnected-(ST1L-P-PadA17)") (class "Default")
      (node (ref "ST1") (pin "A17") (pinfunction "P_A17") (pintype "bidirectional"))
    )
    (net (code "113") (name "unconnected-(ST1M-P-PadA16)") (class "Default")
      (node (ref "ST1") (pin "A16") (pinfunction "P_A16") (pintype "bidirectional"))
    )
    (net (code "114") (name "unconnected-(ST1N-P-PadA15)") (class "Default")
      (node (ref "ST1") (pin "A15") (pinfunction "P_A15") (pintype "bidirectional"))
    )
    (net (code "115") (name "unconnected-(ST1O-P-PadA14)") (class "Default")
      (node (ref "ST1") (pin "A14") (pinfunction "P_A14") (pintype "bidirectional"))
    )
    (net (code "116") (name "unconnected-(ST1P-P-PadA13)") (class "Default")
      (node (ref "ST1") (pin "A13") (pinfunction "P_A13") (pintype "bidirectional"))
    )
    (net (code "117") (name "unconnected-(ST1Q-P-PadA12)") (class "Default")
      (node (ref "ST1") (pin "A12") (pinfunction "P_A12") (pintype "bidirectional"))
    )
  )
)
